# Stepper_Motor2.net
KiCad netlist of a schematic drawn in Altium Designer
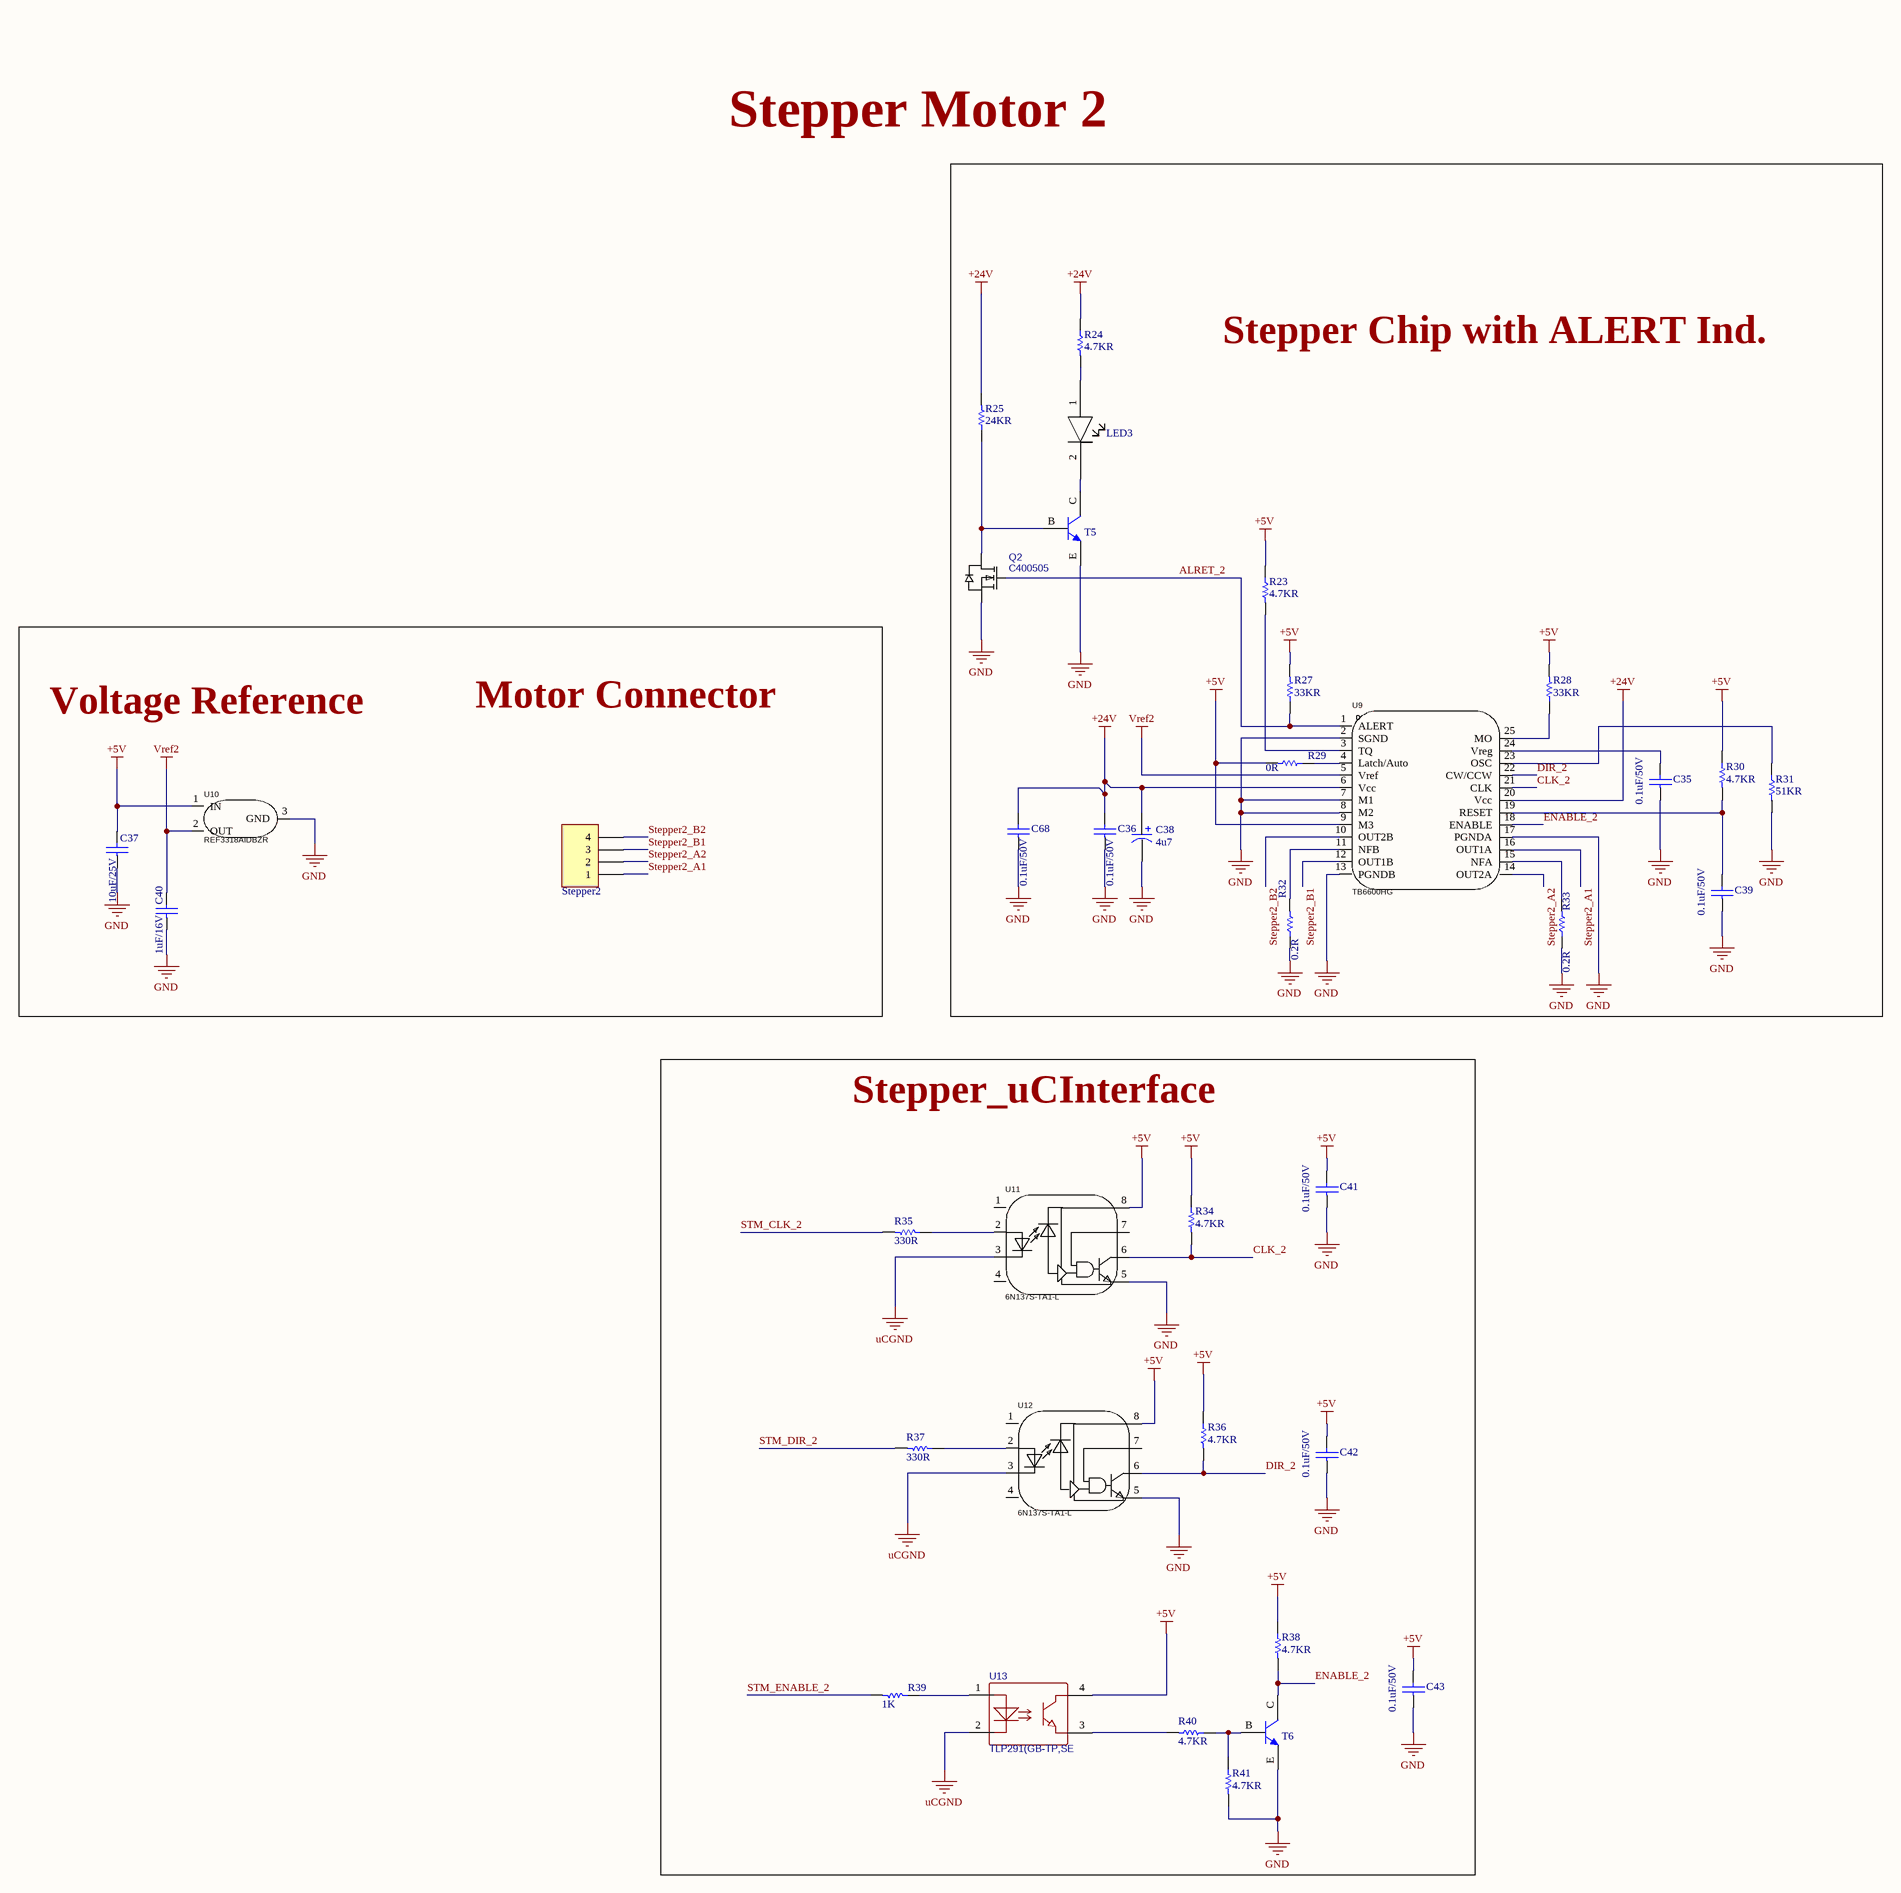
[diagram p0: Stepper Motor2.SchDoc]

(export (version "E")
  (design (tool "Eeschema 10.0.6"))
  (components
    (comp (ref "C35")
      (value "0.1uF/50V")
      (footprint "PCBComponent_1")
      (description "C1591")
      (fields (field (name "CREATED BY") "NourAldin"))
      (libsource (lib "0603 Capacitor") (part "0603 Capacitor"))
    )
    (comp (ref "C36")
      (value "0.1uF/50V")
      (footprint "PCBComponent_1")
      (description "C1591")
      (fields (field (name "CREATED BY") "NourAldin"))
      (libsource (lib "0603 Capacitor") (part "0603 Capacitor"))
    )
    (comp (ref "C37")
      (value "10uF/25V")
      (footprint "PCBComponent_1")
      (description "C96446")
      (fields (field (name "CREATED BY") "NourAldin"))
      (libsource (lib "0603 Capacitor") (part "0603 Capacitor"))
    )
    (comp (ref "C38")
      (value "4u7")
      (footprint "CAPLEAD_D6.3mm")
      (description "C2691843")
      (fields
        (field (name "MANUFACTURER") "KEMET")
        (field (name "MANUFACTURER PART NUMBER") "A759EQ475M2AAAE160")
      )
      (libsource (lib "GlobalLib") (part "A759EQ475M2AAAE160"))
    )
    (comp (ref "C39")
      (value "0.1uF/50V")
      (footprint "PCBComponent_1")
      (description "C1591")
      (fields (field (name "CREATED BY") "NourAldin"))
      (libsource (lib "0603 Capacitor") (part "0603 Capacitor"))
    )
    (comp (ref "C40")
      (value "1uF/16V")
      (footprint "PCBComponent_1")
      (description "C1592")
      (fields (field (name "CREATED BY") "NourAldin"))
      (libsource (lib "0603 Capacitor") (part "0603 Capacitor"))
    )
    (comp (ref "C41")
      (value "0.1uF/50V")
      (footprint "PCBComponent_1")
      (description "C1591")
      (fields (field (name "CREATED BY") "NourAldin"))
      (libsource (lib "0603 Capacitor") (part "0603 Capacitor"))
    )
    (comp (ref "C42")
      (value "0.1uF/50V")
      (footprint "PCBComponent_1")
      (description "C1591")
      (fields (field (name "CREATED BY") "NourAldin"))
      (libsource (lib "0603 Capacitor") (part "0603 Capacitor"))
    )
    (comp (ref "C43")
      (value "0.1uF/50V")
      (footprint "PCBComponent_1")
      (description "C1591")
      (fields (field (name "CREATED BY") "NourAldin"))
      (libsource (lib "0603 Capacitor") (part "0603 Capacitor"))
    )
    (comp (ref "C68")
      (value "0.1uF/50V")
      (footprint "PCBComponent_1")
      (description "C1591")
      (fields (field (name "CREATED BY") "NourAldin"))
      (libsource (lib "0603 Capacitor") (part "0603 Capacitor"))
    )
    (comp (ref "LED3")
      (value "1206 LED")
      (footprint "1206 LED")
      (description "C434438")
      (fields (field (name "CREATED BY") "NourAldin"))
      (libsource (lib "1206 LED") (part "1206 LED"))
    )
    (comp (ref "Q2")
      (value "C400505")
      (footprint "SOT-23-3_L2.9-W1.3-P1.90-LS2.4-BR")
      (fields
        (field (name "MANUFACTURER") "YANGJIE(扬杰)")
        (field (name "MANUFACTURER PART") "BSS138")
        (field (name "CONTRIBUTOR") "LCSC")
      )
      (libsource (lib "DIVERSE") (part "BSS138_MOSFET"))
    )
    (comp (ref "R23")
      (value "4.7KR")
      (footprint "R0402")
      (description "C105871")
      (libsource (lib "DIVERSE") (part "0402 Resistor"))
    )
    (comp (ref "R24")
      (value "4.7KR")
      (footprint "R0402")
      (description "C105871")
      (libsource (lib "DIVERSE") (part "0402 Resistor"))
    )
    (comp (ref "R25")
      (value "24KR")
      (footprint "RESC1608X06N")
      (description "C2930081")
      (fields (field (name "CREATED BY") "NourAldin"))
      (libsource (lib "0603 Resistor") (part "0603 Resistor"))
    )
    (comp (ref "R27")
      (value "33KR")
      (footprint "RESC1608X06N")
      (description "C126359")
      (fields (field (name "CREATED BY") "NourAldin"))
      (libsource (lib "0603 Resistor") (part "0603 Resistor"))
    )
    (comp (ref "R28")
      (value "33KR")
      (footprint "RESC1608X06N")
      (description "C126359")
      (fields (field (name "CREATED BY") "NourAldin"))
      (libsource (lib "0603 Resistor") (part "0603 Resistor"))
    )
    (comp (ref "R29")
      (value "0R")
      (footprint "RESC1608X06N")
      (description "C100044")
      (fields (field (name "CREATED BY") "NourAldin"))
      (libsource (lib "0603 Resistor") (part "0603 Resistor"))
    )
    (comp (ref "R30")
      (value "4.7KR")
      (footprint "R0402")
      (description "C105871")
      (libsource (lib "DIVERSE") (part "0402 Resistor"))
    )
    (comp (ref "R31")
      (value "51KR")
      (footprint "R0402")
      (description "C107230")
      (libsource (lib "DIVERSE") (part "0402 Resistor"))
    )
    (comp (ref "R32")
      (value "0.2R")
      (footprint "RESC6431X12N")
      (description "C2903473")
      (fields (field (name "CREATED BY") "NourAldin"))
      (libsource (lib "2512 Resistor") (part "2512 Resistor"))
    )
    (comp (ref "R33")
      (value "0.2R")
      (footprint "RESC6431X12N")
      (description "C2903473")
      (fields (field (name "CREATED BY") "NourAldin"))
      (libsource (lib "2512 Resistor") (part "2512 Resistor"))
    )
    (comp (ref "R34")
      (value "4.7KR")
      (footprint "R0402")
      (description "C105871")
      (libsource (lib "DIVERSE") (part "0402 Resistor"))
    )
    (comp (ref "R35")
      (value "330R")
      (footprint "R0402")
      (description "C105875")
      (libsource (lib "DIVERSE") (part "0402 Resistor"))
    )
    (comp (ref "R36")
      (value "4.7KR")
      (footprint "R0402")
      (description "C105871")
      (libsource (lib "DIVERSE") (part "0402 Resistor"))
    )
    (comp (ref "R37")
      (value "330R")
      (footprint "R0402")
      (description "C105875")
      (libsource (lib "DIVERSE") (part "0402 Resistor"))
    )
    (comp (ref "R38")
      (value "4.7KR")
      (footprint "R0402")
      (description "C105871")
      (libsource (lib "DIVERSE") (part "0402 Resistor"))
    )
    (comp (ref "R39")
      (value "1K")
      (footprint "R0402")
      (description "C106235")
      (libsource (lib "DIVERSE") (part "0402 Resistor"))
    )
    (comp (ref "R40")
      (value "4.7KR")
      (footprint "R0402")
      (description "C105871")
      (libsource (lib "DIVERSE") (part "0402 Resistor"))
    )
    (comp (ref "R41")
      (value "4.7KR")
      (footprint "R0402")
      (description "C105871")
      (libsource (lib "DIVERSE") (part "0402 Resistor"))
    )
    (comp (ref "Stepper2")
      (value "Header 4 Pin Polar")
      (footprint "PCBComponent_1")
      (description "C144395")
      (libsource (lib "Header 4 Pin Polar") (part "Header 4 Pin Polar"))
    )
    (comp (ref "T5")
      (value "MMBT3904 Transistor")
      (footprint "MMBT3904")
      (description "C108429")
      (fields (field (name "CREATED BY") "NourAldin"))
      (libsource (lib "MMBT3904 Transistor") (part "MMBT3904 Transistor"))
    )
    (comp (ref "T6")
      (value "MMBT3904 Transistor")
      (footprint "MMBT3904")
      (description "C108429")
      (fields (field (name "CREATED BY") "NourAldin"))
      (libsource (lib "MMBT3904 Transistor") (part "MMBT3904 Transistor"))
    )
    (comp (ref "U9")
      (value "TB6600HG")
      (footprint "HZIP25-P-1.0_TB6600HG - HEATSINK")
      (description "C66042")
      (fields (field (name "MANUFACTURER") "TOSHIBA(东芝)"))
      (libsource (lib "LIB") (part "TB6600HG"))
    )
    (comp (ref "U10")
      (value "REF3318AIDBZR")
      (footprint "SOT-23-3_L2.9-W1.3-P1.90-LS2.4-BR")
      (description "C115877")
      (fields (field (name "MANUFACTURER") "TI(德州仪器)") (field (name "TOLERANCE") "±0.15%"))
      (libsource (lib "LIB") (part "REF3318AIDBZR"))
    )
    (comp (ref "U11")
      (value "6N137S-TA1-L")
      (footprint "SOP-8_L9.8-W6.6-P2.54-LS10.3-BL")
      (description "C92651")
      (fields (field (name "MANUFACTURER") "LITEON(光宝)"))
      (libsource (lib "LIB") (part "6N137S-TA1-L"))
    )
    (comp (ref "U12")
      (value "6N137S-TA1-L")
      (footprint "SOP-8_L9.8-W6.6-P2.54-LS10.3-BL")
      (description "C92651")
      (fields (field (name "MANUFACTURER") "LITEON(光宝)"))
      (libsource (lib "LIB") (part "6N137S-TA1-L"))
    )
    (comp (ref "U13")
      (value "TLP291(GB-TP,SE")
      (footprint "SOP-4-1.27mm")
      (description "C55144")
      (libsource (lib "CO2_Lib") (part "TLP291(GB-TP,SE(T"))
    )
  )
  (nets
    (net (code "1") (name "+5V") (class "Default")
      (node (ref "C37") (pin "2") (pinfunction "2_2") (pintype "passive"))
      (node (ref "C41") (pin "2") (pinfunction "2_2") (pintype "passive"))
      (node (ref "C42") (pin "2") (pinfunction "2_2") (pintype "passive"))
      (node (ref "C43") (pin "2") (pinfunction "2_2") (pintype "passive"))
      (node (ref "R23") (pin "1") (pinfunction "1_1") (pintype "passive"))
      (node (ref "R27") (pin "2") (pinfunction "2_2") (pintype "passive"))
      (node (ref "R28") (pin "2") (pinfunction "2_2") (pintype "passive"))
      (node (ref "R29") (pin "2") (pinfunction "2_2") (pintype "passive"))
      (node (ref "R30") (pin "1") (pinfunction "1_1") (pintype "passive"))
      (node (ref "R34") (pin "1") (pinfunction "1_1") (pintype "passive"))
      (node (ref "R36") (pin "1") (pinfunction "1_1") (pintype "passive"))
      (node (ref "R38") (pin "1") (pinfunction "1_1") (pintype "passive"))
      (node (ref "U10") (pin "1") (pinfunction "IN_1") (pintype "passive"))
      (node (ref "U11") (pin "8") (pinfunction "8_8") (pintype "passive"))
      (node (ref "U12") (pin "8") (pinfunction "8_8") (pintype "passive"))
      (node (ref "U13") (pin "4") (pinfunction "4_4") (pintype "passive"))
      (node (ref "U9") (pin "9") (pinfunction "M3_9") (pintype "passive"))
    )
    (net (code "2") (name "+24V") (class "Default")
      (node (ref "C36") (pin "2") (pinfunction "2_2") (pintype "passive"))
      (node (ref "C38") (pin "1") (pinfunction "1_1") (pintype "passive"))
      (node (ref "C68") (pin "2") (pinfunction "2_2") (pintype "passive"))
      (node (ref "R24") (pin "1") (pinfunction "1_1") (pintype "passive"))
      (node (ref "R25") (pin "2") (pinfunction "2_2") (pintype "passive"))
      (node (ref "U9") (pin "20") (pinfunction "Vcc_20") (pintype "passive"))
      (node (ref "U9") (pin "6") (pinfunction "Vcc_6") (pintype "passive"))
    )
    (net (code "3") (name "/ALRET_2") (class "Default")
      (node (ref "Q2") (pin "1") (pinfunction "G_1") (pintype "passive"))
      (node (ref "R27") (pin "1") (pinfunction "1_1") (pintype "passive"))
      (node (ref "U9") (pin "1") (pinfunction "ALERT_1") (pintype "passive"))
    )
    (net (code "4") (name "/CLK_2") (class "Default")
      (node (ref "R34") (pin "2") (pinfunction "2_2") (pintype "passive"))
      (node (ref "U11") (pin "6") (pinfunction "6_6") (pintype "passive"))
      (node (ref "U9") (pin "21") (pinfunction "CLK_21") (pintype "passive"))
    )
    (net (code "5") (name "/DIR_2") (class "Default")
      (node (ref "R36") (pin "2") (pinfunction "2_2") (pintype "passive"))
      (node (ref "U12") (pin "6") (pinfunction "6_6") (pintype "passive"))
      (node (ref "U9") (pin "22") (pinfunction "CW/CCW_22") (pintype "passive"))
    )
    (net (code "6") (name "/ENABLE_2") (class "Default")
      (node (ref "R38") (pin "2") (pinfunction "2_2") (pintype "passive"))
      (node (ref "T6") (pin "C") (pinfunction "C_C") (pintype "passive"))
      (node (ref "U9") (pin "18") (pinfunction "ENABLE_18") (pintype "passive"))
    )
    (net (code "7") (name "/STM_CLK_2") (class "Default")
      (node (ref "R35") (pin "2") (pinfunction "2_2") (pintype "passive"))
    )
    (net (code "8") (name "/STM_DIR_2") (class "Default")
      (node (ref "R37") (pin "2") (pinfunction "2_2") (pintype "passive"))
    )
    (net (code "9") (name "/STM_ENABLE_2") (class "Default")
      (node (ref "R39") (pin "2") (pinfunction "2_2") (pintype "passive"))
    )
    (net (code "10") (name "/Stepper2_A1") (class "Default")
      (node (ref "Stepper2") (pin "1") (pinfunction "1_1") (pintype "passive"))
      (node (ref "U9") (pin "16") (pinfunction "OUT1A_16") (pintype "passive"))
    )
    (net (code "11") (name "/Stepper2_A2") (class "Default")
      (node (ref "Stepper2") (pin "2") (pinfunction "2_2") (pintype "passive"))
      (node (ref "U9") (pin "14") (pinfunction "OUT2A_14") (pintype "passive"))
    )
    (net (code "12") (name "/Stepper2_B1") (class "Default")
      (node (ref "Stepper2") (pin "3") (pinfunction "3_3") (pintype "passive"))
      (node (ref "U9") (pin "12") (pinfunction "OUT1B_12") (pintype "passive"))
    )
    (net (code "13") (name "/Stepper2_B2") (class "Default")
      (node (ref "Stepper2") (pin "4") (pinfunction "4_4") (pintype "passive"))
      (node (ref "U9") (pin "10") (pinfunction "OUT2B_10") (pintype "passive"))
    )
    (net (code "14") (name "GND") (class "Default")
      (node (ref "C35") (pin "1") (pinfunction "1_1") (pintype "passive"))
      (node (ref "C36") (pin "1") (pinfunction "1_1") (pintype "passive"))
      (node (ref "C37") (pin "1") (pinfunction "1_1") (pintype "passive"))
      (node (ref "C38") (pin "2") (pinfunction "2_2") (pintype "passive"))
      (node (ref "C39") (pin "1") (pinfunction "1_1") (pintype "passive"))
      (node (ref "C40") (pin "1") (pinfunction "1_1") (pintype "passive"))
      (node (ref "C41") (pin "1") (pinfunction "1_1") (pintype "passive"))
      (node (ref "C42") (pin "1") (pinfunction "1_1") (pintype "passive"))
      (node (ref "C43") (pin "1") (pinfunction "1_1") (pintype "passive"))
      (node (ref "C68") (pin "1") (pinfunction "1_1") (pintype "passive"))
      (node (ref "Q2") (pin "2") (pinfunction "S_2") (pintype "passive"))
      (node (ref "R31") (pin "2") (pinfunction "2_2") (pintype "passive"))
      (node (ref "R32") (pin "1") (pinfunction "1_1") (pintype "passive"))
      (node (ref "R33") (pin "1") (pinfunction "1_1") (pintype "passive"))
      (node (ref "R41") (pin "2") (pinfunction "2_2") (pintype "passive"))
      (node (ref "T5") (pin "E") (pinfunction "E_E") (pintype "passive"))
      (node (ref "T6") (pin "E") (pinfunction "E_E") (pintype "passive"))
      (node (ref "U10") (pin "3") (pinfunction "GND_3") (pintype "passive"))
      (node (ref "U11") (pin "5") (pinfunction "5_5") (pintype "passive"))
      (node (ref "U12") (pin "5") (pinfunction "5_5") (pintype "passive"))
      (node (ref "U9") (pin "13") (pinfunction "PGNDB_13") (pintype "passive"))
      (node (ref "U9") (pin "17") (pinfunction "PGNDA_17") (pintype "passive"))
      (node (ref "U9") (pin "2") (pinfunction "SGND_2") (pintype "passive"))
      (node (ref "U9") (pin "7") (pinfunction "M1_7") (pintype "passive"))
      (node (ref "U9") (pin "8") (pinfunction "M2_8") (pintype "passive"))
    )
    (net (code "15") (name "Net-(LED3-Pad1)") (class "Default")
      (node (ref "LED3") (pin "1") (pinfunction "1_1") (pintype "passive"))
      (node (ref "R24") (pin "2") (pinfunction "2_2") (pintype "passive"))
    )
    (net (code "16") (name "Net-(LED3-Pad2)") (class "Default")
      (node (ref "LED3") (pin "2") (pinfunction "2_2") (pintype "passive"))
      (node (ref "T5") (pin "C") (pinfunction "C_C") (pintype "passive"))
    )
    (net (code "17") (name "Net-(Q2-D)") (class "Default")
      (node (ref "Q2") (pin "3") (pinfunction "D_3") (pintype "passive"))
      (node (ref "R25") (pin "1") (pinfunction "1_1") (pintype "passive"))
      (node (ref "T5") (pin "B") (pinfunction "B_B") (pintype "passive"))
    )
    (net (code "18") (name "Net-(R35-Pad1)") (class "Default")
      (node (ref "R35") (pin "1") (pinfunction "1_1") (pintype "passive"))
      (node (ref "U11") (pin "2") (pinfunction "2_2") (pintype "passive"))
    )
    (net (code "19") (name "Net-(R37-Pad1)") (class "Default")
      (node (ref "R37") (pin "1") (pinfunction "1_1") (pintype "passive"))
      (node (ref "U12") (pin "2") (pinfunction "2_2") (pintype "passive"))
    )
    (net (code "20") (name "Net-(R39-Pad1)") (class "Default")
      (node (ref "R39") (pin "1") (pinfunction "1_1") (pintype "passive"))
      (node (ref "U13") (pin "1") (pinfunction "1_1") (pintype "passive"))
    )
    (net (code "21") (name "Net-(R40-Pad1)") (class "Default")
      (node (ref "R40") (pin "1") (pinfunction "1_1") (pintype "passive"))
      (node (ref "R41") (pin "1") (pinfunction "1_1") (pintype "passive"))
      (node (ref "T6") (pin "B") (pinfunction "B_B") (pintype "passive"))
    )
    (net (code "22") (name "Net-(R40-Pad2)") (class "Default")
      (node (ref "R40") (pin "2") (pinfunction "2_2") (pintype "passive"))
      (node (ref "U13") (pin "3") (pinfunction "3_3") (pintype "passive"))
    )
    (net (code "23") (name "Net-(U9-Latch{slash}Auto)") (class "Default")
      (node (ref "R29") (pin "1") (pinfunction "1_1") (pintype "passive"))
      (node (ref "U9") (pin "4") (pinfunction "Latch/Auto_4") (pintype "passive"))
    )
    (net (code "24") (name "Net-(U9-MO)") (class "Default")
      (node (ref "R28") (pin "1") (pinfunction "1_1") (pintype "passive"))
      (node (ref "U9") (pin "25") (pinfunction "MO_25") (pintype "passive"))
    )
    (net (code "25") (name "Net-(U9-NFA)") (class "Default")
      (node (ref "R33") (pin "2") (pinfunction "2_2") (pintype "passive"))
      (node (ref "U9") (pin "15") (pinfunction "NFA_15") (pintype "passive"))
    )
    (net (code "26") (name "Net-(U9-NFB)") (class "Default")
      (node (ref "R32") (pin "2") (pinfunction "2_2") (pintype "passive"))
      (node (ref "U9") (pin "11") (pinfunction "NFB_11") (pintype "passive"))
    )
    (net (code "27") (name "Net-(U9-OSC)") (class "Default")
      (node (ref "R31") (pin "1") (pinfunction "1_1") (pintype "passive"))
      (node (ref "U9") (pin "23") (pinfunction "OSC_23") (pintype "passive"))
    )
    (net (code "28") (name "Net-(U9-RESET)") (class "Default")
      (node (ref "C39") (pin "2") (pinfunction "2_2") (pintype "passive"))
      (node (ref "R30") (pin "2") (pinfunction "2_2") (pintype "passive"))
      (node (ref "U9") (pin "19") (pinfunction "RESET_19") (pintype "passive"))
    )
    (net (code "29") (name "Net-(U9-TQ)") (class "Default")
      (node (ref "R23") (pin "2") (pinfunction "2_2") (pintype "passive"))
      (node (ref "U9") (pin "3") (pinfunction "TQ_3") (pintype "passive"))
    )
    (net (code "30") (name "Net-(U9-Vreg)") (class "Default")
      (node (ref "C35") (pin "2") (pinfunction "2_2") (pintype "passive"))
      (node (ref "U9") (pin "24") (pinfunction "Vreg_24") (pintype "passive"))
    )
    (net (code "31") (name "Vref2") (class "Default")
      (node (ref "C40") (pin "2") (pinfunction "2_2") (pintype "passive"))
      (node (ref "U10") (pin "2") (pinfunction "OUT_2") (pintype "passive"))
      (node (ref "U9") (pin "5") (pinfunction "Vref_5") (pintype "passive"))
    )
    (net (code "32") (name "uCGND") (class "Default")
      (node (ref "U11") (pin "3") (pinfunction "3_3") (pintype "passive"))
      (node (ref "U12") (pin "3") (pinfunction "3_3") (pintype "passive"))
      (node (ref "U13") (pin "2") (pinfunction "2_2") (pintype "passive"))
    )
    (net (code "33") (name "unconnected-(U11-NC-Pad1)") (class "Default")
      (node (ref "U11") (pin "1") (pinfunction "NC_1") (pintype "passive"))
    )
    (net (code "34") (name "unconnected-(U11-NC-Pad4)") (class "Default")
      (node (ref "U11") (pin "4") (pinfunction "NC_4") (pintype "passive"))
    )
    (net (code "35") (name "unconnected-(U11-Pad7)") (class "Default")
      (node (ref "U11") (pin "7") (pinfunction "7_7") (pintype "passive"))
    )
    (net (code "36") (name "unconnected-(U12-NC-Pad1)") (class "Default")
      (node (ref "U12") (pin "1") (pinfunction "NC_1") (pintype "passive"))
    )
    (net (code "37") (name "unconnected-(U12-NC-Pad4)") (class "Default")
      (node (ref "U12") (pin "4") (pinfunction "NC_4") (pintype "passive"))
    )
    (net (code "38") (name "unconnected-(U12-Pad7)") (class "Default")
      (node (ref "U12") (pin "7") (pinfunction "7_7") (pintype "passive"))
    )
  )
)
